# RS485.net
KiCad netlist of a schematic drawn in Altium Designer
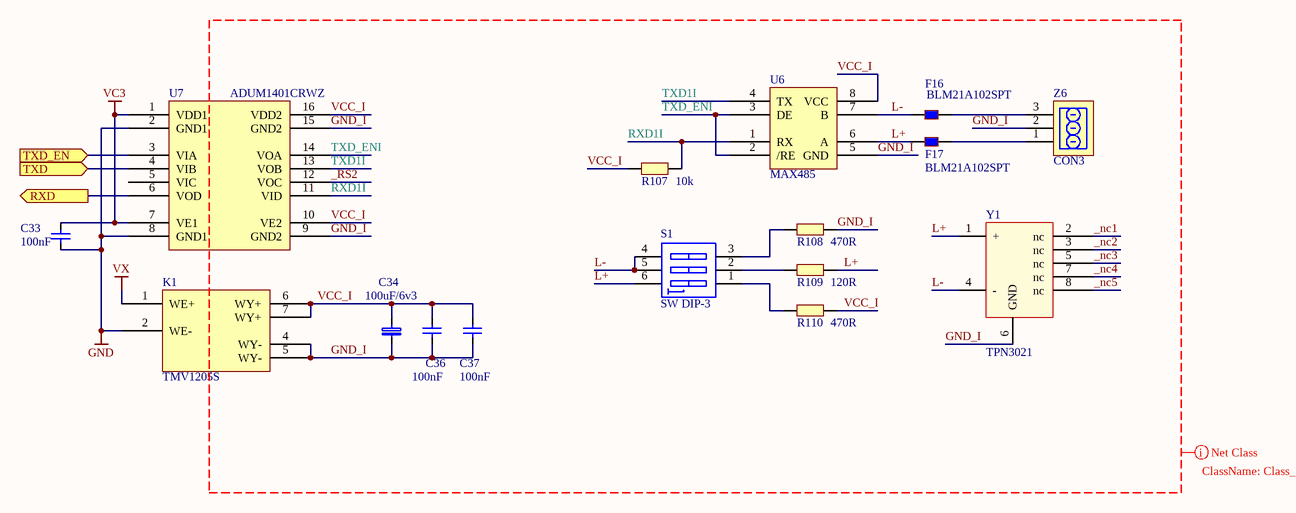
[diagram p0: RS485.SchDoc]

(export (version "E")
  (design (tool "Eeschema 10.0.6"))
  (components
    (comp (ref "C33") (value "100nF") (footprint "0603C") (libsource (lib "*") (part "CAP")))
    (comp (ref "C34")
      (value "100uF/6v3")
      (footprint "CAP_C")
      (description "KONDENSATOR ELEKTROLITYCZNY TANTALOWY SMD")
      (libsource (lib "*") (part "CAP_TANTAL_SMD"))
    )
    (comp (ref "C36") (value "100nF") (footprint "0603C") (libsource (lib "*") (part "CAP")))
    (comp (ref "C37") (value "100nF") (footprint "0603C") (libsource (lib "*") (part "CAP")))
    (comp (ref "F16")
      (value "BLM21A102SPT")
      (footprint "0603L")
      (description "Koralik ferrytowy")
      (libsource (lib "*") (part "KORALIK"))
    )
    (comp (ref "F17")
      (value "BLM21A102SPT")
      (footprint "0603L")
      (description "Koralik ferrytowy")
      (libsource (lib "*") (part "KORALIK"))
    )
    (comp (ref "K1") (value "TMV1205S") (footprint "DCDC-S1_D") (libsource (lib "*") (part "NMV0505S_D")))
    (comp (ref "R107") (value "10k") (footprint "0603R") (libsource (lib "*") (part "RES3")))
    (comp (ref "R108") (value "470R") (footprint "1206") (libsource (lib "*") (part "RES3")))
    (comp (ref "R109") (value "120R") (footprint "1206") (libsource (lib "*") (part "RES3")))
    (comp (ref "R110") (value "470R") (footprint "1206") (libsource (lib "*") (part "RES3")))
    (comp (ref "S1")
      (value "SW DIP-3")
      (footprint "DIP-6")
      (description "DIP Switch, 3 Position, SPST")
      (fields (field (name "PUBLISHER") "Altium Limited"))
      (libsource (lib "Miscellaneous Devices") (part "SW DIP-3"))
    )
    (comp (ref "U6") (value "MAX485") (footprint "SO8") (libsource (lib "*") (part "MAX485_1")))
    (comp (ref "U7") (value "ADUM1401CRWZ") (footprint "SMD16B") (libsource (lib "*") (part "ADUM1401")))
    (comp (ref "Y1") (value "TPN3021") (footprint "SO8") (libsource (lib "GkSchlib") (part "TPN3021")))
    (comp (ref "Z6") (value "CON3") (footprint "ARC-3-3.5-TYCO-1") (libsource (lib "*") (part "ZL-3")))
  )
  (nets
    (net (code "1") (name "/GND_I") (class "Default")
      (node (ref "C34") (pin "1") (pintype "passive"))
      (node (ref "C36") (pin "2") (pintype "passive"))
      (node (ref "C37") (pin "2") (pintype "passive"))
      (node (ref "K1") (pin "4") (pinfunction "WY-_4") (pintype "passive"))
      (node (ref "K1") (pin "5") (pinfunction "WY-_5") (pintype "passive"))
      (node (ref "R108") (pin "2") (pintype "passive"))
      (node (ref "U6") (pin "5") (pinfunction "GND_5") (pintype "passive"))
      (node (ref "U7") (pin "15") (pinfunction "GND2_15") (pintype "passive"))
      (node (ref "U7") (pin "9") (pinfunction "GND2_9") (pintype "passive"))
      (node (ref "Y1") (pin "6") (pinfunction "GND_6") (pintype "passive"))
      (node (ref "Z6") (pin "2") (pintype "passive"))
    )
    (net (code "2") (name "/L+") (class "Default")
      (node (ref "F17") (pin "1") (pintype "passive"))
      (node (ref "R109") (pin "2") (pintype "passive"))
      (node (ref "S1") (pin "6") (pinfunction "B1_6") (pintype "passive"))
      (node (ref "U6") (pin "6") (pinfunction "A_6") (pintype "passive"))
      (node (ref "Y1") (pin "1") (pinfunction "+_1") (pintype "passive"))
    )
    (net (code "3") (name "/L-") (class "Default")
      (node (ref "F16") (pin "1") (pintype "passive"))
      (node (ref "S1") (pin "4") (pinfunction "B3_4") (pintype "passive"))
      (node (ref "S1") (pin "5") (pinfunction "B2_5") (pintype "passive"))
      (node (ref "U6") (pin "7") (pinfunction "B_7") (pintype "passive"))
      (node (ref "Y1") (pin "4") (pinfunction "-_4") (pintype "passive"))
    )
    (net (code "4") (name "/RXD") (class "Default")
      (node (ref "U7") (pin "6") (pinfunction "VOD_6") (pintype "passive"))
    )
    (net (code "5") (name "/RXD1I") (class "Default")
      (node (ref "R107") (pin "2") (pintype "passive"))
      (node (ref "U6") (pin "1") (pinfunction "RX_1") (pintype "passive"))
      (node (ref "U7") (pin "11") (pinfunction "VID_11") (pintype "passive"))
    )
    (net (code "6") (name "/TXD") (class "Default")
      (node (ref "U7") (pin "4") (pinfunction "VIB_4") (pintype "passive"))
    )
    (net (code "7") (name "/TXD1I") (class "Default")
      (node (ref "U6") (pin "4") (pinfunction "TX_4") (pintype "passive"))
      (node (ref "U7") (pin "13") (pinfunction "VOB_13") (pintype "passive"))
    )
    (net (code "8") (name "/TXD_EN") (class "Default")
      (node (ref "U7") (pin "3") (pinfunction "VIA_3") (pintype "passive"))
    )
    (net (code "9") (name "/TXD_ENI") (class "Default")
      (node (ref "U6") (pin "2") (pinfunction "/RE_2") (pintype "passive"))
      (node (ref "U6") (pin "3") (pinfunction "DE_3") (pintype "passive"))
      (node (ref "U7") (pin "14") (pinfunction "VOA_14") (pintype "passive"))
    )
    (net (code "10") (name "/VCC_I") (class "Default")
      (node (ref "C34") (pin "2") (pintype "passive"))
      (node (ref "C36") (pin "1") (pintype "passive"))
      (node (ref "C37") (pin "1") (pintype "passive"))
      (node (ref "K1") (pin "6") (pinfunction "WY+_6") (pintype "passive"))
      (node (ref "K1") (pin "7") (pinfunction "WY+_7") (pintype "passive"))
      (node (ref "R107") (pin "1") (pintype "passive"))
      (node (ref "R110") (pin "2") (pintype "passive"))
      (node (ref "U6") (pin "8") (pinfunction "VCC_8") (pintype "passive"))
      (node (ref "U7") (pin "10") (pinfunction "VE2_10") (pintype "passive"))
      (node (ref "U7") (pin "16") (pinfunction "VDD2_16") (pintype "passive"))
    )
    (net (code "11") (name "/_RS2") (class "Default")
      (node (ref "U7") (pin "12") (pinfunction "VOC_12") (pintype "passive"))
    )
    (net (code "12") (name "/_nc1") (class "Default")
      (node (ref "Y1") (pin "2") (pinfunction "nc_2") (pintype "passive"))
    )
    (net (code "13") (name "/_nc2") (class "Default")
      (node (ref "Y1") (pin "3") (pinfunction "nc_3") (pintype "passive"))
    )
    (net (code "14") (name "/_nc3") (class "Default")
      (node (ref "Y1") (pin "5") (pinfunction "nc_5") (pintype "passive"))
    )
    (net (code "15") (name "/_nc4") (class "Default")
      (node (ref "Y1") (pin "7") (pinfunction "nc_7") (pintype "passive"))
    )
    (net (code "16") (name "/_nc5") (class "Default")
      (node (ref "Y1") (pin "8") (pinfunction "nc_8") (pintype "passive"))
    )
    (net (code "17") (name "GND") (class "Default")
      (node (ref "C33") (pin "2") (pintype "passive"))
      (node (ref "K1") (pin "2") (pinfunction "WE-_2") (pintype "passive"))
      (node (ref "U7") (pin "2") (pinfunction "GND1_2") (pintype "passive"))
      (node (ref "U7") (pin "8") (pinfunction "GND1_8") (pintype "passive"))
    )
    (net (code "18") (name "Net-(F16-Pad2)") (class "Default")
      (node (ref "F16") (pin "2") (pintype "passive"))
      (node (ref "Z6") (pin "3") (pintype "passive"))
    )
    (net (code "19") (name "Net-(F17-Pad2)") (class "Default")
      (node (ref "F17") (pin "2") (pintype "passive"))
      (node (ref "Z6") (pin "1") (pintype "passive"))
    )
    (net (code "20") (name "Net-(S1-A1)") (class "Default")
      (node (ref "R110") (pin "1") (pintype "passive"))
      (node (ref "S1") (pin "1") (pinfunction "A1_1") (pintype "passive"))
    )
    (net (code "21") (name "Net-(S1-A2)") (class "Default")
      (node (ref "R109") (pin "1") (pintype "passive"))
      (node (ref "S1") (pin "2") (pinfunction "A2_2") (pintype "passive"))
    )
    (net (code "22") (name "Net-(S1-A3)") (class "Default")
      (node (ref "R108") (pin "1") (pintype "passive"))
      (node (ref "S1") (pin "3") (pinfunction "A3_3") (pintype "passive"))
    )
    (net (code "23") (name "VC3") (class "Default")
      (node (ref "C33") (pin "1") (pintype "passive"))
      (node (ref "U7") (pin "1") (pinfunction "VDD1_1") (pintype "passive"))
      (node (ref "U7") (pin "7") (pinfunction "VE1_7") (pintype "passive"))
    )
    (net (code "24") (name "VX") (class "Default")
      (node (ref "K1") (pin "1") (pinfunction "WE+_1") (pintype "passive"))
    )
    (net (code "25") (name "unconnected-(U7-VIC-Pad5)") (class "Default")
      (node (ref "U7") (pin "5") (pinfunction "VIC_5") (pintype "passive"))
    )
  )
)
